# Sensors.net
KiCad netlist of a schematic drawn in Altium Designer
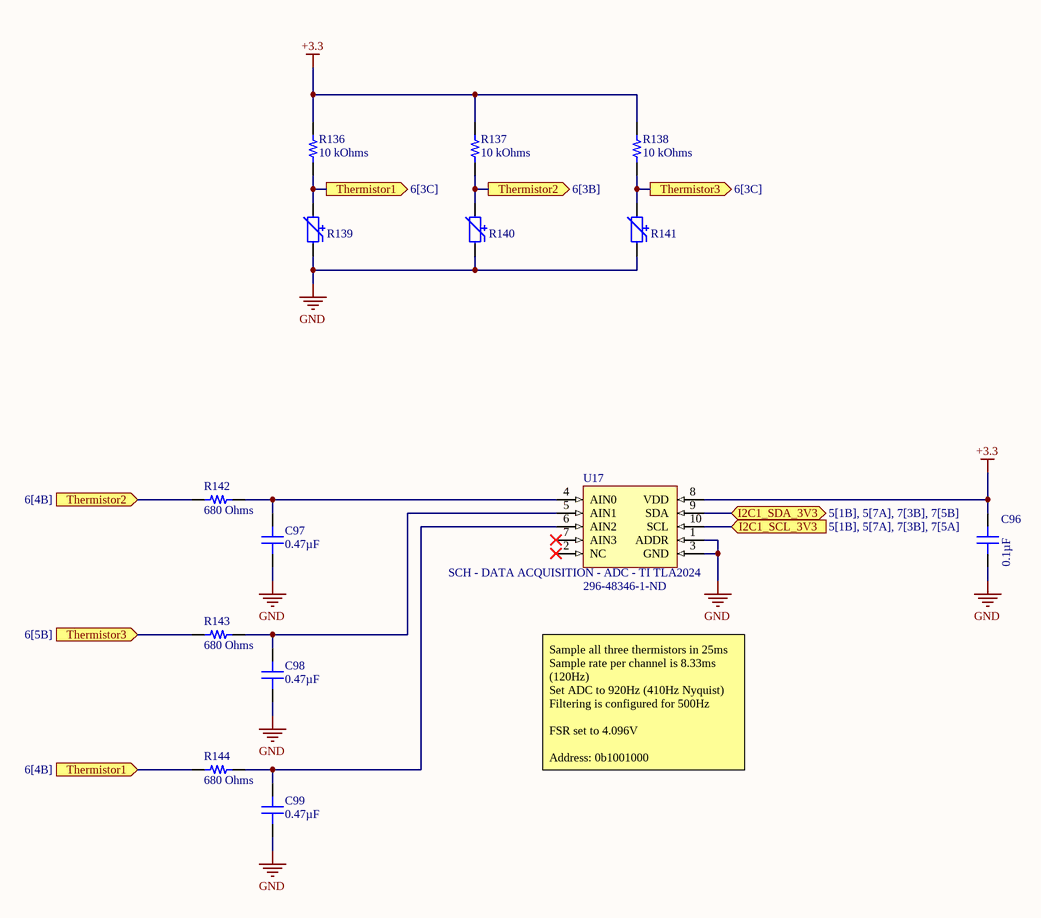
[diagram p0: Sensors.SchDoc]

(export (version "E")
  (design (tool "Eeschema 10.0.6"))
  (components
    (comp (ref "C96")
      (value "0.1µF")
      (footprint "CAP 0603_1608")
      (description "CAP CER 0.1UF 25V X7R 0603")
      (fields
        (field (name "PART NUMBER") "CL10B104KA8WPNC")
        (field (name "MANUFACTURER") "Samsung Electro-Mechanics")
      )
      (libsource (lib "Celestial Altium Library - altium_library") (part "Capacitor"))
    )
    (comp (ref "C97")
      (value "0.47µF")
      (footprint "CAP 0603_1608")
      (description "CAP CER 0.47UF 16V X5R 0603")
      (fields (field (name "PART NUMBER") "C0603C474K4PACTU") (field (name "MANUFACTURER") "KEMET"))
      (libsource (lib "Celestial Altium Library - altium_library") (part "Capacitor"))
    )
    (comp (ref "C98")
      (value "0.47µF")
      (footprint "CAP 0603_1608")
      (description "CAP CER 0.47UF 16V X5R 0603")
      (fields (field (name "PART NUMBER") "C0603C474K4PACTU") (field (name "MANUFACTURER") "KEMET"))
      (libsource (lib "Celestial Altium Library - altium_library") (part "Capacitor"))
    )
    (comp (ref "C99")
      (value "0.47µF")
      (footprint "CAP 0603_1608")
      (description "CAP CER 0.47UF 16V X5R 0603")
      (fields (field (name "PART NUMBER") "C0603C474K4PACTU") (field (name "MANUFACTURER") "KEMET"))
      (libsource (lib "Celestial Altium Library - altium_library") (part "Capacitor"))
    )
    (comp (ref "R136")
      (value "10 kOhms")
      (footprint "RES 0603_1608")
      (description "RES 10K OHM 1% 1/10W 0603")
      (fields
        (field (name "PART NUMBER") "RMCF0603FT10K0")
        (field (name "MANUFACTURER") "Stackpole Electronics Inc")
      )
      (libsource (lib "Celestial Altium Library - altium_library") (part "Resistor"))
    )
    (comp (ref "R137")
      (value "10 kOhms")
      (footprint "RES 0603_1608")
      (description "RES 10K OHM 1% 1/10W 0603")
      (fields
        (field (name "PART NUMBER") "RMCF0603FT10K0")
        (field (name "MANUFACTURER") "Stackpole Electronics Inc")
      )
      (libsource (lib "Celestial Altium Library - altium_library") (part "Resistor"))
    )
    (comp (ref "R138")
      (value "10 kOhms")
      (footprint "RES 0603_1608")
      (description "RES 10K OHM 1% 1/10W 0603")
      (fields
        (field (name "PART NUMBER") "RMCF0603FT10K0")
        (field (name "MANUFACTURER") "Stackpole Electronics Inc")
      )
      (libsource (lib "Celestial Altium Library - altium_library") (part "Resistor"))
    )
    (comp (ref "R139")
      (value "10 kOhms")
      (footprint "PTC 0402_1005")
      (description "SENSOR PTC 10KOHM 1% X1SON")
      (fields (field (name "MANUFACTURER") "Texas Instruments") (field (name "PART NUMBER") "TMP6131DECR"))
      (libsource (lib "Celestial Altium Library - altium_library") (part "Thermistor PTC"))
    )
    (comp (ref "R140")
      (value "10 kOhms")
      (footprint "PTC 0402_1005")
      (description "SENSOR PTC 10KOHM 1% X1SON")
      (fields (field (name "MANUFACTURER") "Texas Instruments") (field (name "PART NUMBER") "TMP6131DECR"))
      (libsource (lib "Celestial Altium Library - altium_library") (part "Thermistor PTC"))
    )
    (comp (ref "R141")
      (value "10 kOhms")
      (footprint "PTC 0402_1005")
      (description "SENSOR PTC 10KOHM 1% X1SON")
      (fields (field (name "MANUFACTURER") "Texas Instruments") (field (name "PART NUMBER") "TMP6131DECR"))
      (libsource (lib "Celestial Altium Library - altium_library") (part "Thermistor PTC"))
    )
    (comp (ref "R142")
      (value "680 Ohms")
      (footprint "RES 0603_1608")
      (description "RES 680 OHM 1% 1/10W 0603")
      (fields
        (field (name "PART NUMBER") "RMCF0603FT680R")
        (field (name "MANUFACTURER") "Stackpole Electronics Inc")
      )
      (libsource (lib "Celestial Altium Library - altium_library") (part "Resistor"))
    )
    (comp (ref "R143")
      (value "680 Ohms")
      (footprint "RES 0603_1608")
      (description "RES 680 OHM 1% 1/10W 0603")
      (fields
        (field (name "PART NUMBER") "RMCF0603FT680R")
        (field (name "MANUFACTURER") "Stackpole Electronics Inc")
      )
      (libsource (lib "Celestial Altium Library - altium_library") (part "Resistor"))
    )
    (comp (ref "R144")
      (value "680 Ohms")
      (footprint "RES 0603_1608")
      (description "RES 680 OHM 1% 1/10W 0603")
      (fields
        (field (name "PART NUMBER") "RMCF0603FT680R")
        (field (name "MANUFACTURER") "Stackpole Electronics Inc")
      )
      (libsource (lib "Celestial Altium Library - altium_library") (part "Resistor"))
    )
    (comp (ref "U17")
      (value "SCH - DATA ACQUISITION - ADC - TI TLA2024")
      (footprint "PCB - LEADLESS - QFN - TI X2QFN-10")
      (fields (field (name "SUPPLIER PART NUMBER 1") "296-48346-1-ND"))
      (libsource (lib "HAB_ICs") (part "SCH - DATA ACQUISITION - ADC - TI TLA2024"))
    )
  )
  (nets
    (net (code "1") (name "+3.3") (class "Default")
      (node (ref "C96") (pin "2") (pinfunction "2_2") (pintype "passive"))
      (node (ref "R136") (pin "2") (pinfunction "2_2") (pintype "passive"))
      (node (ref "R137") (pin "2") (pinfunction "2_2") (pintype "passive"))
      (node (ref "R138") (pin "2") (pinfunction "2_2") (pintype "passive"))
      (node (ref "U17") (pin "8") (pinfunction "VDD_8") (pintype "input"))
    )
    (net (code "2") (name "/I2C1_SCL_3V3") (class "Default")
      (node (ref "U17") (pin "10") (pinfunction "SCL_10") (pintype "input"))
    )
    (net (code "3") (name "/I2C1_SDA_3V3") (class "Default")
      (node (ref "U17") (pin "9") (pinfunction "SDA_9") (pintype "input"))
    )
    (net (code "4") (name "/Thermistor1") (class "Default")
      (node (ref "R136") (pin "1") (pinfunction "1_1") (pintype "passive"))
      (node (ref "R139") (pin "2") (pinfunction "2_2") (pintype "passive"))
      (node (ref "R144") (pin "1") (pinfunction "1_1") (pintype "passive"))
    )
    (net (code "5") (name "/Thermistor2") (class "Default")
      (node (ref "R137") (pin "1") (pinfunction "1_1") (pintype "passive"))
      (node (ref "R140") (pin "2") (pinfunction "2_2") (pintype "passive"))
      (node (ref "R142") (pin "1") (pinfunction "1_1") (pintype "passive"))
    )
    (net (code "6") (name "/Thermistor3") (class "Default")
      (node (ref "R138") (pin "1") (pinfunction "1_1") (pintype "passive"))
      (node (ref "R141") (pin "2") (pinfunction "2_2") (pintype "passive"))
      (node (ref "R143") (pin "1") (pinfunction "1_1") (pintype "passive"))
    )
    (net (code "7") (name "GND") (class "Default")
      (node (ref "C96") (pin "1") (pinfunction "1_1") (pintype "passive"))
      (node (ref "C97") (pin "1") (pinfunction "1_1") (pintype "passive"))
      (node (ref "C98") (pin "1") (pinfunction "1_1") (pintype "passive"))
      (node (ref "C99") (pin "1") (pinfunction "1_1") (pintype "passive"))
      (node (ref "R139") (pin "1") (pinfunction "1_1") (pintype "passive"))
      (node (ref "R140") (pin "1") (pinfunction "1_1") (pintype "passive"))
      (node (ref "R141") (pin "1") (pinfunction "1_1") (pintype "passive"))
      (node (ref "U17") (pin "1") (pinfunction "ADDR_1") (pintype "input"))
      (node (ref "U17") (pin "3") (pinfunction "GND_3") (pintype "input"))
    )
    (net (code "8") (name "Net-(U17-AIN0)") (class "Default")
      (node (ref "C97") (pin "2") (pinfunction "2_2") (pintype "passive"))
      (node (ref "R142") (pin "2") (pinfunction "2_2") (pintype "passive"))
      (node (ref "U17") (pin "4") (pinfunction "AIN0_4") (pintype "input"))
    )
    (net (code "9") (name "Net-(U17-AIN1)") (class "Default")
      (node (ref "C98") (pin "2") (pinfunction "2_2") (pintype "passive"))
      (node (ref "R143") (pin "2") (pinfunction "2_2") (pintype "passive"))
      (node (ref "U17") (pin "5") (pinfunction "AIN1_5") (pintype "input"))
    )
    (net (code "10") (name "Net-(U17-AIN2)") (class "Default")
      (node (ref "C99") (pin "2") (pinfunction "2_2") (pintype "passive"))
      (node (ref "R144") (pin "2") (pinfunction "2_2") (pintype "passive"))
      (node (ref "U17") (pin "6") (pinfunction "AIN2_6") (pintype "input"))
    )
    (net (code "11") (name "unconnected-(U17-AIN3-Pad7)") (class "Default")
      (node (ref "U17") (pin "7") (pinfunction "AIN3_7") (pintype "input+no_connect"))
    )
    (net (code "12") (name "unconnected-(U17-NC-Pad2)") (class "Default")
      (node (ref "U17") (pin "2") (pinfunction "NC_2") (pintype "input+no_connect"))
    )
  )
)
